# receiver.net
KiCad netlist of a schematic drawn in EAGLE
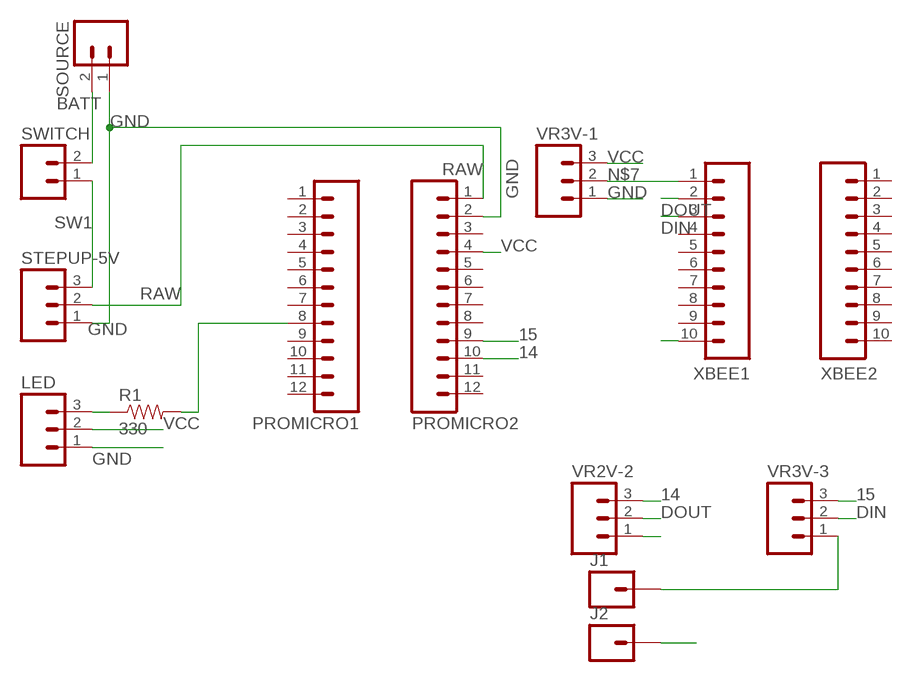
[diagram p0: schematic, sheet 1]

(export (version "E")
  (design (tool "Eeschema 10.0.6"))
  (components
    (comp (ref "J1")
      (value "M01PTH")
      (footprint "eagle-import:1X01")
      (libsource (lib "eagle-import") (part "M01PTH"))
    )
    (comp (ref "J2")
      (value "M01PTH")
      (footprint "eagle-import:1X01")
      (libsource (lib "eagle-import") (part "M01PTH"))
    )
    (comp (ref "LED")
      (value "M03LOCK")
      (footprint "eagle-import:1X03_LOCK")
      (libsource (lib "eagle-import") (part "M03LOCK"))
    )
    (comp (ref "PROMICRO1")
      (value "M12LOCK")
      (footprint "eagle-import:1X12_LOCK")
      (libsource (lib "eagle-import") (part "M12LOCK"))
    )
    (comp (ref "PROMICRO2")
      (value "M12LOCK")
      (footprint "eagle-import:1X12_LOCK")
      (libsource (lib "eagle-import") (part "M12LOCK"))
    )
    (comp (ref "R1")
      (value "330")
      (footprint "eagle-import:AXIAL-0.4")
      (libsource (lib "eagle-import") (part "RESISTORPTH-1/4W"))
    )
    (comp (ref "SOURCE")
      (value "M02JST-PTH-VERT")
      (footprint "eagle-import:JST-2-PTH-VERT")
      (libsource (lib "eagle-import") (part "M02JST-PTH-VERT"))
    )
    (comp (ref "STEPUP-5V")
      (value "M03LOCK")
      (footprint "eagle-import:1X03_LOCK")
      (libsource (lib "eagle-import") (part "M03LOCK"))
    )
    (comp (ref "SWITCH")
      (value "M02LOCK")
      (footprint "eagle-import:1X02_LOCK")
      (libsource (lib "eagle-import") (part "M02LOCK"))
    )
    (comp (ref "VR2V-2")
      (value "M03LOCK")
      (footprint "eagle-import:1X03_LOCK")
      (libsource (lib "eagle-import") (part "M03LOCK"))
    )
    (comp (ref "VR3V-1")
      (value "M03LOCK")
      (footprint "eagle-import:1X03_LOCK")
      (libsource (lib "eagle-import") (part "M03LOCK"))
    )
    (comp (ref "VR3V-3")
      (value "M03LOCK")
      (footprint "eagle-import:1X03_LOCK")
      (libsource (lib "eagle-import") (part "M03LOCK"))
    )
    (comp (ref "XBEE1")
      (value "M10LOCK")
      (footprint "eagle-import:1X10_LOCK")
      (libsource (lib "eagle-import") (part "M10LOCK"))
    )
    (comp (ref "XBEE2")
      (value "M10LOCK")
      (footprint "eagle-import:1X10_LOCK")
      (libsource (lib "eagle-import") (part "M10LOCK"))
    )
  )
  (nets
    (net (code "1") (name "/14") (class "Default")
      (node (ref "PROMICRO2") (pin "10") (pinfunction "10_10") (pintype "passive"))
      (node (ref "VR2V-2") (pin "3") (pinfunction "3_3") (pintype "passive"))
    )
    (net (code "2") (name "/15") (class "Default")
      (node (ref "PROMICRO2") (pin "9") (pinfunction "9_9") (pintype "passive"))
      (node (ref "VR3V-3") (pin "3") (pinfunction "3_3") (pintype "passive"))
    )
    (net (code "3") (name "/BATT") (class "Default")
      (node (ref "SOURCE") (pin "2") (pinfunction "2_2") (pintype "passive"))
      (node (ref "SWITCH") (pin "2") (pinfunction "2_2") (pintype "passive"))
    )
    (net (code "4") (name "/DIN") (class "Default")
      (node (ref "VR3V-3") (pin "2") (pinfunction "2_2") (pintype "passive"))
      (node (ref "XBEE1") (pin "3") (pinfunction "3_3") (pintype "passive"))
    )
    (net (code "5") (name "/DOUT") (class "Default")
      (node (ref "VR2V-2") (pin "2") (pinfunction "2_2") (pintype "passive"))
      (node (ref "XBEE1") (pin "2") (pinfunction "2_2") (pintype "passive"))
    )
    (net (code "6") (name "/GND") (class "Default")
      (node (ref "J1") (pin "1") (pinfunction "1_1") (pintype "passive"))
      (node (ref "J2") (pin "1") (pinfunction "1_1") (pintype "passive"))
      (node (ref "LED") (pin "1") (pinfunction "1_1") (pintype "passive"))
      (node (ref "PROMICRO2") (pin "2") (pinfunction "2_2") (pintype "passive"))
      (node (ref "SOURCE") (pin "1") (pinfunction "1_1") (pintype "passive"))
      (node (ref "STEPUP-5V") (pin "1") (pinfunction "1_1") (pintype "passive"))
      (node (ref "VR2V-2") (pin "1") (pinfunction "1_1") (pintype "passive"))
      (node (ref "VR3V-1") (pin "1") (pinfunction "1_1") (pintype "passive"))
      (node (ref "VR3V-3") (pin "1") (pinfunction "1_1") (pintype "passive"))
    )
    (net (code "7") (name "/N$7") (class "Default")
      (node (ref "VR3V-1") (pin "2") (pinfunction "2_2") (pintype "passive"))
      (node (ref "XBEE1") (pin "1") (pinfunction "1_1") (pintype "passive"))
    )
    (net (code "8") (name "/RAW") (class "Default")
      (node (ref "PROMICRO2") (pin "1") (pinfunction "1_1") (pintype "passive"))
      (node (ref "STEPUP-5V") (pin "2") (pinfunction "2_2") (pintype "passive"))
    )
    (net (code "9") (name "/SW1") (class "Default")
      (node (ref "STEPUP-5V") (pin "3") (pinfunction "3_3") (pintype "passive"))
      (node (ref "SWITCH") (pin "1") (pinfunction "1_1") (pintype "passive"))
    )
    (net (code "10") (name "/VCC") (class "Default")
      (node (ref "LED") (pin "2") (pinfunction "2_2") (pintype "passive"))
      (node (ref "PROMICRO2") (pin "4") (pinfunction "4_4") (pintype "passive"))
      (node (ref "VR3V-1") (pin "3") (pinfunction "3_3") (pintype "passive"))
    )
    (net (code "11") (name "Net-(R1-1)") (class "Default")
      (node (ref "LED") (pin "3") (pinfunction "3_3") (pintype "passive"))
      (node (ref "R1") (pin "P$1") (pinfunction "1_P$1") (pintype "passive"))
    )
    (net (code "12") (name "Net-(R1-2)") (class "Default")
      (node (ref "PROMICRO1") (pin "8") (pinfunction "8_8") (pintype "passive"))
      (node (ref "R1") (pin "P$2") (pinfunction "2_P$2") (pintype "passive"))
    )
    (net (code "13") (name "unconnected-(PROMICRO1-Pad1)") (class "Default")
      (node (ref "PROMICRO1") (pin "1") (pinfunction "1_1") (pintype "passive"))
    )
    (net (code "14") (name "unconnected-(PROMICRO1-Pad2)") (class "Default")
      (node (ref "PROMICRO1") (pin "2") (pinfunction "2_2") (pintype "passive"))
    )
    (net (code "15") (name "unconnected-(PROMICRO1-Pad3)") (class "Default")
      (node (ref "PROMICRO1") (pin "3") (pinfunction "3_3") (pintype "passive"))
    )
    (net (code "16") (name "unconnected-(PROMICRO1-Pad4)") (class "Default")
      (node (ref "PROMICRO1") (pin "4") (pinfunction "4_4") (pintype "passive"))
    )
    (net (code "17") (name "unconnected-(PROMICRO1-Pad5)") (class "Default")
      (node (ref "PROMICRO1") (pin "5") (pinfunction "5_5") (pintype "passive"))
    )
    (net (code "18") (name "unconnected-(PROMICRO1-Pad6)") (class "Default")
      (node (ref "PROMICRO1") (pin "6") (pinfunction "6_6") (pintype "passive"))
    )
    (net (code "19") (name "unconnected-(PROMICRO1-Pad7)") (class "Default")
      (node (ref "PROMICRO1") (pin "7") (pinfunction "7_7") (pintype "passive"))
    )
    (net (code "20") (name "unconnected-(PROMICRO1-Pad9)") (class "Default")
      (node (ref "PROMICRO1") (pin "9") (pinfunction "9_9") (pintype "passive"))
    )
    (net (code "21") (name "unconnected-(PROMICRO1-Pad10)") (class "Default")
      (node (ref "PROMICRO1") (pin "10") (pinfunction "10_10") (pintype "passive"))
    )
    (net (code "22") (name "unconnected-(PROMICRO1-Pad11)") (class "Default")
      (node (ref "PROMICRO1") (pin "11") (pinfunction "11_11") (pintype "passive"))
    )
    (net (code "23") (name "unconnected-(PROMICRO1-Pad12)") (class "Default")
      (node (ref "PROMICRO1") (pin "12") (pinfunction "12_12") (pintype "passive"))
    )
    (net (code "24") (name "unconnected-(PROMICRO2-Pad3)") (class "Default")
      (node (ref "PROMICRO2") (pin "3") (pinfunction "3_3") (pintype "passive"))
    )
    (net (code "25") (name "unconnected-(PROMICRO2-Pad5)") (class "Default")
      (node (ref "PROMICRO2") (pin "5") (pinfunction "5_5") (pintype "passive"))
    )
    (net (code "26") (name "unconnected-(PROMICRO2-Pad6)") (class "Default")
      (node (ref "PROMICRO2") (pin "6") (pinfunction "6_6") (pintype "passive"))
    )
    (net (code "27") (name "unconnected-(PROMICRO2-Pad7)") (class "Default")
      (node (ref "PROMICRO2") (pin "7") (pinfunction "7_7") (pintype "passive"))
    )
    (net (code "28") (name "unconnected-(PROMICRO2-Pad8)") (class "Default")
      (node (ref "PROMICRO2") (pin "8") (pinfunction "8_8") (pintype "passive"))
    )
    (net (code "29") (name "unconnected-(PROMICRO2-Pad11)") (class "Default")
      (node (ref "PROMICRO2") (pin "11") (pinfunction "11_11") (pintype "passive"))
    )
    (net (code "30") (name "unconnected-(PROMICRO2-Pad12)") (class "Default")
      (node (ref "PROMICRO2") (pin "12") (pinfunction "12_12") (pintype "passive"))
    )
    (net (code "31") (name "unconnected-(XBEE1-Pad4)") (class "Default")
      (node (ref "XBEE1") (pin "4") (pinfunction "4_4") (pintype "passive"))
    )
    (net (code "32") (name "unconnected-(XBEE1-Pad5)") (class "Default")
      (node (ref "XBEE1") (pin "5") (pinfunction "5_5") (pintype "passive"))
    )
    (net (code "33") (name "unconnected-(XBEE1-Pad6)") (class "Default")
      (node (ref "XBEE1") (pin "6") (pinfunction "6_6") (pintype "passive"))
    )
    (net (code "34") (name "unconnected-(XBEE1-Pad7)") (class "Default")
      (node (ref "XBEE1") (pin "7") (pinfunction "7_7") (pintype "passive"))
    )
    (net (code "35") (name "unconnected-(XBEE1-Pad8)") (class "Default")
      (node (ref "XBEE1") (pin "8") (pinfunction "8_8") (pintype "passive"))
    )
    (net (code "36") (name "unconnected-(XBEE1-Pad9)") (class "Default")
      (node (ref "XBEE1") (pin "9") (pinfunction "9_9") (pintype "passive"))
    )
    (net (code "37") (name "unconnected-(XBEE1-Pad10)") (class "Default")
      (node (ref "XBEE1") (pin "10") (pinfunction "10_10") (pintype "passive"))
    )
    (net (code "38") (name "unconnected-(XBEE2-Pad1)") (class "Default")
      (node (ref "XBEE2") (pin "1") (pinfunction "1_1") (pintype "passive"))
    )
    (net (code "39") (name "unconnected-(XBEE2-Pad2)") (class "Default")
      (node (ref "XBEE2") (pin "2") (pinfunction "2_2") (pintype "passive"))
    )
    (net (code "40") (name "unconnected-(XBEE2-Pad3)") (class "Default")
      (node (ref "XBEE2") (pin "3") (pinfunction "3_3") (pintype "passive"))
    )
    (net (code "41") (name "unconnected-(XBEE2-Pad4)") (class "Default")
      (node (ref "XBEE2") (pin "4") (pinfunction "4_4") (pintype "passive"))
    )
    (net (code "42") (name "unconnected-(XBEE2-Pad5)") (class "Default")
      (node (ref "XBEE2") (pin "5") (pinfunction "5_5") (pintype "passive"))
    )
    (net (code "43") (name "unconnected-(XBEE2-Pad6)") (class "Default")
      (node (ref "XBEE2") (pin "6") (pinfunction "6_6") (pintype "passive"))
    )
    (net (code "44") (name "unconnected-(XBEE2-Pad7)") (class "Default")
      (node (ref "XBEE2") (pin "7") (pinfunction "7_7") (pintype "passive"))
    )
    (net (code "45") (name "unconnected-(XBEE2-Pad8)") (class "Default")
      (node (ref "XBEE2") (pin "8") (pinfunction "8_8") (pintype "passive"))
    )
    (net (code "46") (name "unconnected-(XBEE2-Pad9)") (class "Default")
      (node (ref "XBEE2") (pin "9") (pinfunction "9_9") (pintype "passive"))
    )
    (net (code "47") (name "unconnected-(XBEE2-Pad10)") (class "Default")
      (node (ref "XBEE2") (pin "10") (pinfunction "10_10") (pintype "passive"))
    )
  )
)
